# DG5-shield_v1_5.net
KiCad netlist of a schematic drawn in EAGLE
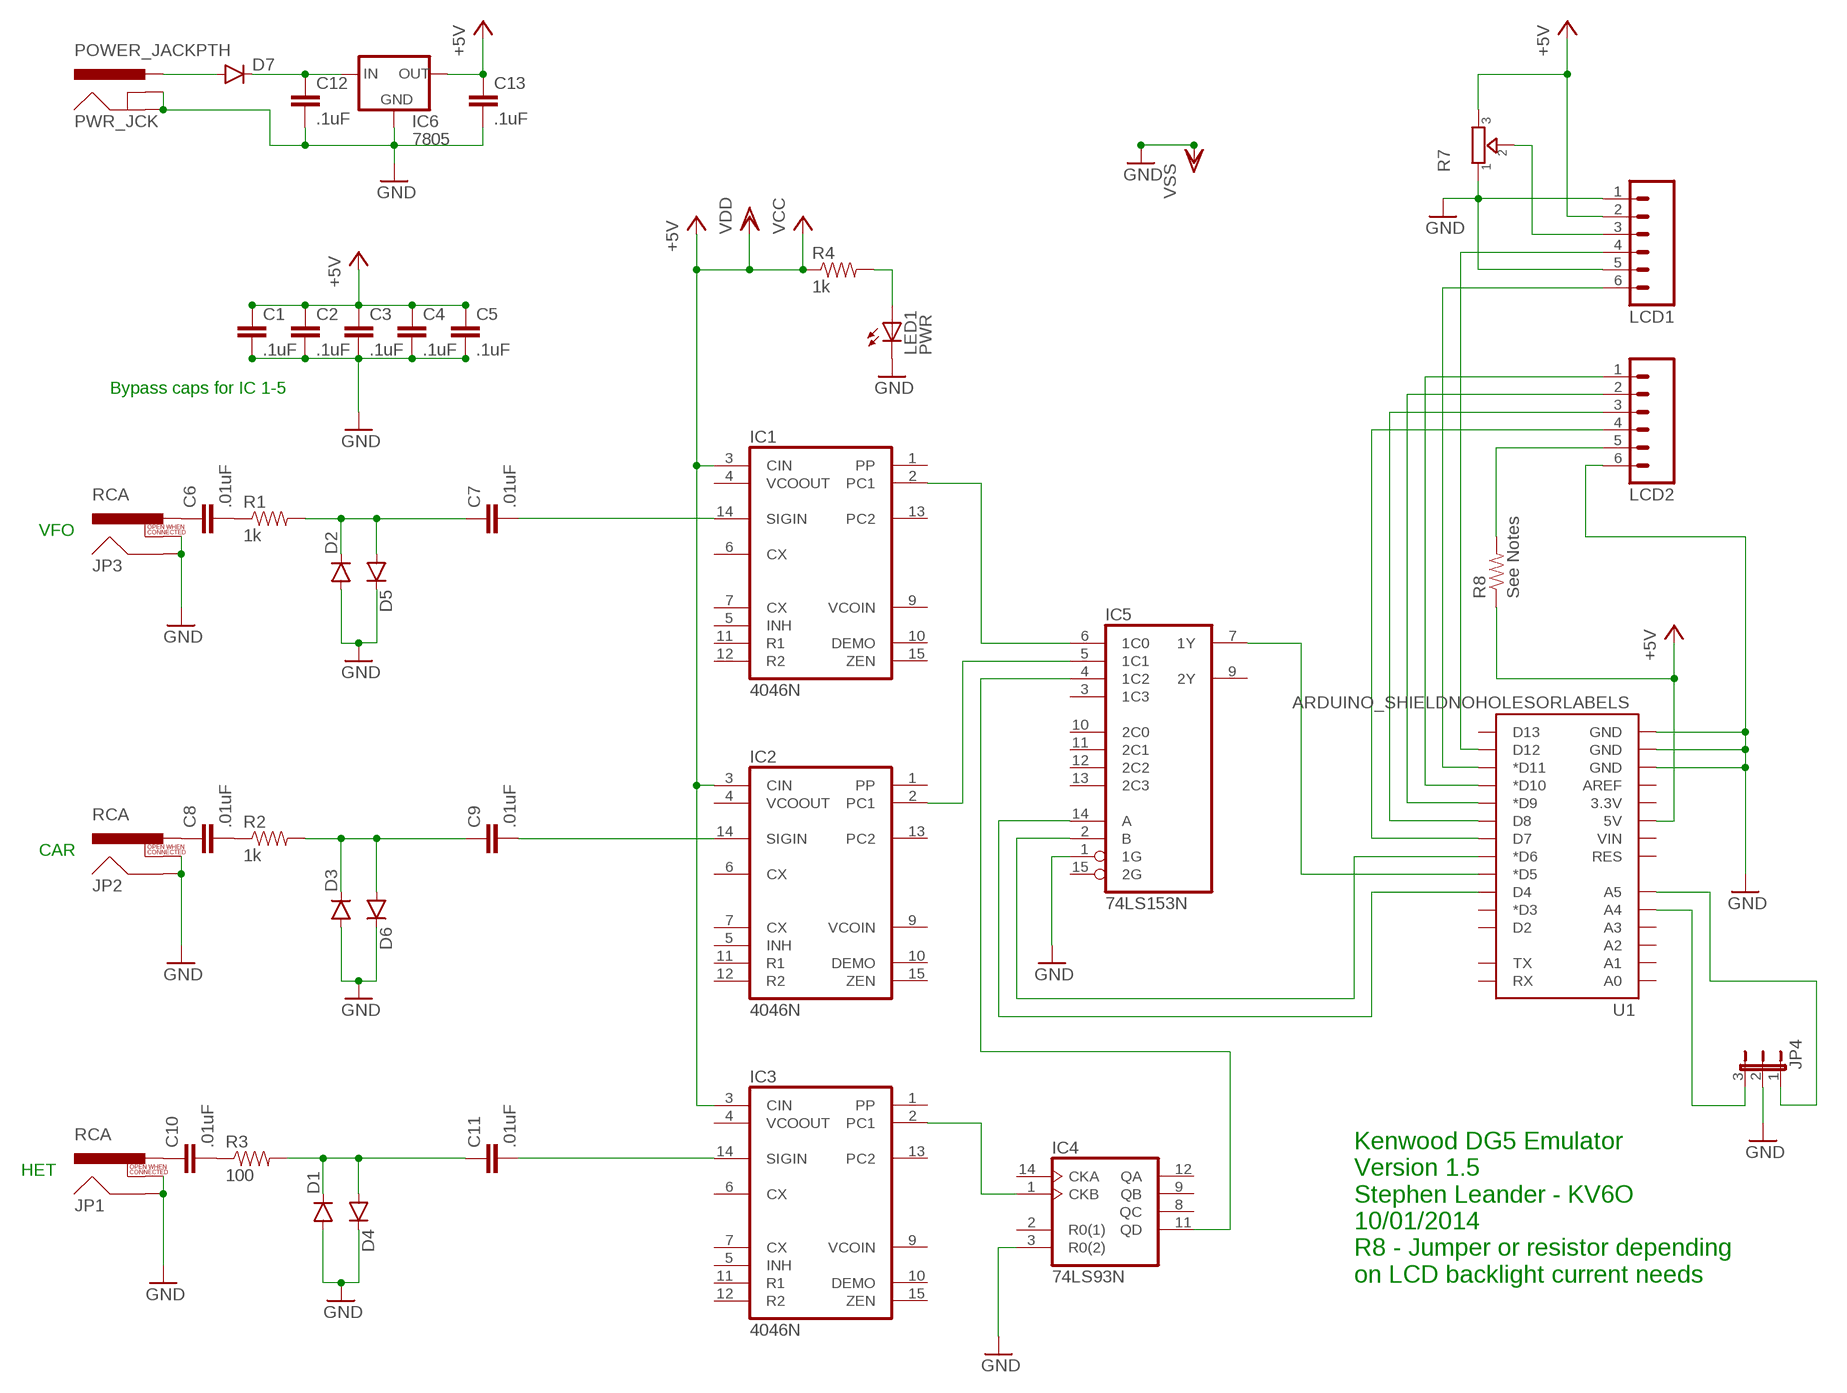
[diagram p0: schematic, sheet 1]

(export (version "E")
  (design (tool "Eeschema 10.0.6"))
  (components
    (comp (ref "C1")
      (value ".1uF")
      (footprint "eagle-import:CAP-PTH-SMALL-KIT")
      (libsource (lib "eagle-import") (part "CAPKIT"))
    )
    (comp (ref "C2")
      (value ".1uF")
      (footprint "eagle-import:CAP-PTH-SMALL-KIT")
      (libsource (lib "eagle-import") (part "CAPKIT"))
    )
    (comp (ref "C3")
      (value ".1uF")
      (footprint "eagle-import:CAP-PTH-SMALL-KIT")
      (libsource (lib "eagle-import") (part "CAPKIT"))
    )
    (comp (ref "C4")
      (value ".1uF")
      (footprint "eagle-import:CAP-PTH-SMALL-KIT")
      (libsource (lib "eagle-import") (part "CAPKIT"))
    )
    (comp (ref "C5")
      (value ".1uF")
      (footprint "eagle-import:CAP-PTH-SMALL-KIT")
      (libsource (lib "eagle-import") (part "CAPKIT"))
    )
    (comp (ref "C6")
      (value ".01uF")
      (footprint "eagle-import:CAP-PTH-SMALL-KIT")
      (libsource (lib "eagle-import") (part "CAPKIT"))
    )
    (comp (ref "C7")
      (value ".01uF")
      (footprint "eagle-import:CAP-PTH-SMALL-KIT")
      (libsource (lib "eagle-import") (part "CAPKIT"))
    )
    (comp (ref "C8")
      (value ".01uF")
      (footprint "eagle-import:CAP-PTH-SMALL-KIT")
      (libsource (lib "eagle-import") (part "CAPKIT"))
    )
    (comp (ref "C9")
      (value ".01uF")
      (footprint "eagle-import:CAP-PTH-SMALL-KIT")
      (libsource (lib "eagle-import") (part "CAPKIT"))
    )
    (comp (ref "C10")
      (value ".01uF")
      (footprint "eagle-import:CAP-PTH-SMALL-KIT")
      (libsource (lib "eagle-import") (part "CAPKIT"))
    )
    (comp (ref "C11")
      (value ".01uF")
      (footprint "eagle-import:CAP-PTH-SMALL-KIT")
      (libsource (lib "eagle-import") (part "CAPKIT"))
    )
    (comp (ref "C12")
      (value ".1uF")
      (footprint "eagle-import:CAP-PTH-SMALL-KIT")
      (libsource (lib "eagle-import") (part "CAPKIT"))
    )
    (comp (ref "C13")
      (value ".1uF")
      (footprint "eagle-import:CAP-PTH-SMALL-KIT")
      (libsource (lib "eagle-import") (part "CAPKIT"))
    )
    (comp (ref "D1")
      (value "DIODE1N4148")
      (footprint "eagle-import:DIODE-1N4148")
      (libsource (lib "eagle-import") (part "DIODE1N4148"))
    )
    (comp (ref "D2")
      (value "DIODE1N4148")
      (footprint "eagle-import:DIODE-1N4148")
      (libsource (lib "eagle-import") (part "DIODE1N4148"))
    )
    (comp (ref "D3")
      (value "DIODE1N4148")
      (footprint "eagle-import:DIODE-1N4148")
      (libsource (lib "eagle-import") (part "DIODE1N4148"))
    )
    (comp (ref "D4")
      (value "DIODE1N4148")
      (footprint "eagle-import:DIODE-1N4148")
      (libsource (lib "eagle-import") (part "DIODE1N4148"))
    )
    (comp (ref "D5")
      (value "DIODE1N4148")
      (footprint "eagle-import:DIODE-1N4148")
      (libsource (lib "eagle-import") (part "DIODE1N4148"))
    )
    (comp (ref "D6")
      (value "DIODE1N4148")
      (footprint "eagle-import:DIODE-1N4148")
      (libsource (lib "eagle-import") (part "DIODE1N4148"))
    )
    (comp (ref "D7")
      (value "DIODE")
      (footprint "eagle-import:DIODE-1N4001-KIT")
      (libsource (lib "eagle-import") (part "DIODE"))
    )
    (comp (ref "IC1")
      (value "4046N")
      (footprint "eagle-import:DIL16")
      (libsource (lib "eagle-import") (part "4046N"))
    )
    (comp (ref "IC2")
      (value "4046N")
      (footprint "eagle-import:DIL16")
      (libsource (lib "eagle-import") (part "4046N"))
    )
    (comp (ref "IC3")
      (value "4046N")
      (footprint "eagle-import:DIL16")
      (libsource (lib "eagle-import") (part "4046N"))
    )
    (comp (ref "IC4")
      (value "74LS93N")
      (footprint "eagle-import:DIL14")
      (libsource (lib "eagle-import") (part "7493NLS"))
    )
    (comp (ref "IC5")
      (value "74LS153N")
      (footprint "eagle-import:DIL16")
      (libsource (lib "eagle-import") (part "74153NLS"))
    )
    (comp (ref "IC6")
      (value "7805")
      (footprint "eagle-import:TO220-IGO")
      (libsource (lib "eagle-import") (part "V_REG_78XXSINK"))
    )
    (comp (ref "JP1")
      (value "RCA")
      (footprint "eagle-import:RCA")
      (libsource (lib "eagle-import") (part "RCA"))
    )
    (comp (ref "JP2")
      (value "RCA")
      (footprint "eagle-import:RCA")
      (libsource (lib "eagle-import") (part "RCA"))
    )
    (comp (ref "JP3")
      (value "RCA")
      (footprint "eagle-import:RCA")
      (libsource (lib "eagle-import") (part "RCA"))
    )
    (comp (ref "JP4")
      (value "JP2E")
      (footprint "eagle-import:JP2")
      (libsource (lib "eagle-import") (part "JP2E"))
    )
    (comp (ref "LCD1")
      (value "M06SIP")
      (footprint "eagle-import:1X06")
      (libsource (lib "eagle-import") (part "M06SIP"))
    )
    (comp (ref "LCD2")
      (value "M06SIP")
      (footprint "eagle-import:1X06")
      (libsource (lib "eagle-import") (part "M06SIP"))
    )
    (comp (ref "LED1")
      (value "PWR")
      (footprint "eagle-import:LED3MM")
      (fields (field (name "MF") "VISHAY SEMICONDUCTOR"))
      (libsource (lib "eagle-import") (part "TLLG4400"))
    )
    (comp (ref "PWR_JCK")
      (value "POWER_JACKPTH")
      (footprint "eagle-import:POWER_JACK_PTH")
      (libsource (lib "eagle-import") (part "POWER_JACKPTH"))
    )
    (comp (ref "R1")
      (value "1k")
      (footprint "eagle-import:1_6W-RES")
      (libsource (lib "eagle-import") (part "RESISTORPTH-1/6W"))
    )
    (comp (ref "R2")
      (value "1k")
      (footprint "eagle-import:1_6W-RES")
      (libsource (lib "eagle-import") (part "RESISTORPTH-1/6W"))
    )
    (comp (ref "R3")
      (value "100")
      (footprint "eagle-import:1_6W-RES")
      (libsource (lib "eagle-import") (part "RESISTORPTH-1/6W"))
    )
    (comp (ref "R4")
      (value "1k")
      (footprint "eagle-import:1_6W-RES")
      (libsource (lib "eagle-import") (part "RESISTORPTH-1/6W"))
    )
    (comp (ref "R7")
      (value "TRIMMER-3306F")
      (footprint "eagle-import:TRIMMER_3306F")
      (libsource (lib "eagle-import") (part "TRIMMER-3306F"))
    )
    (comp (ref "R8")
      (value "See Notes")
      (footprint "eagle-import:1_6W-RES")
      (libsource (lib "eagle-import") (part "RESISTORPTH-1/6W"))
    )
    (comp (ref "U1")
      (value "ARDUINO_SHIELDNOHOLESORLABELS")
      (footprint "eagle-import:DUEMILANOVE_SHIELD_NOHOLES_NOLABELS")
      (libsource (lib "eagle-import") (part "ARDUINO_SHIELDNOHOLESORLABELS"))
    )
  )
  (nets
    (net (code "1") (name "+5V") (class "Default")
      (node (ref "C1") (pin "1") (pinfunction "1_1") (pintype "passive"))
      (node (ref "C13") (pin "1") (pinfunction "1_1") (pintype "passive"))
      (node (ref "C2") (pin "1") (pinfunction "1_1") (pintype "passive"))
      (node (ref "C3") (pin "1") (pinfunction "1_1") (pintype "passive"))
      (node (ref "C4") (pin "1") (pinfunction "1_1") (pintype "passive"))
      (node (ref "C5") (pin "1") (pinfunction "1_1") (pintype "passive"))
      (node (ref "IC1") (pin "3") (pinfunction "CIN_3") (pintype "input"))
      (node (ref "IC2") (pin "3") (pinfunction "CIN_3") (pintype "input"))
      (node (ref "IC3") (pin "3") (pinfunction "CIN_3") (pintype "input"))
      (node (ref "IC6") (pin "OUT") (pinfunction "OUT_OUT") (pintype "output"))
      (node (ref "LCD1") (pin "2") (pinfunction "2_2") (pintype "passive"))
      (node (ref "R4") (pin "1") (pinfunction "1_1") (pintype "passive"))
      (node (ref "R7") (pin "3") (pinfunction "3_3") (pintype "passive"))
      (node (ref "R8") (pin "1") (pinfunction "1_1") (pintype "passive"))
      (node (ref "U1") (pin "5V") (pinfunction "5V_5V") (pintype "bidirectional"))
    )
    (net (code "2") (name "GND") (class "Default")
      (node (ref "C1") (pin "2") (pinfunction "2_2") (pintype "passive"))
      (node (ref "C12") (pin "2") (pinfunction "2_2") (pintype "passive"))
      (node (ref "C13") (pin "2") (pinfunction "2_2") (pintype "passive"))
      (node (ref "C2") (pin "2") (pinfunction "2_2") (pintype "passive"))
      (node (ref "C3") (pin "2") (pinfunction "2_2") (pintype "passive"))
      (node (ref "C4") (pin "2") (pinfunction "2_2") (pintype "passive"))
      (node (ref "C5") (pin "2") (pinfunction "2_2") (pintype "passive"))
      (node (ref "D1") (pin "A") (pinfunction "A_A") (pintype "passive"))
      (node (ref "D2") (pin "A") (pinfunction "A_A") (pintype "passive"))
      (node (ref "D3") (pin "A") (pinfunction "A_A") (pintype "passive"))
      (node (ref "D4") (pin "C") (pinfunction "C_C") (pintype "passive"))
      (node (ref "D5") (pin "C") (pinfunction "C_C") (pintype "passive"))
      (node (ref "D6") (pin "C") (pinfunction "C_C") (pintype "passive"))
      (node (ref "IC4") (pin "3") (pinfunction "R0(2)_3") (pintype "input"))
      (node (ref "IC5") (pin "1") (pinfunction "1G_1") (pintype "input"))
      (node (ref "IC6") (pin "GND") (pinfunction "GND_GND") (pintype "input"))
      (node (ref "JP1") (pin "SHELL") (pinfunction "SHELL_SHELL") (pintype "bidirectional"))
      (node (ref "JP1") (pin "SWITCH") (pinfunction "SWITCH_SWITCH") (pintype "bidirectional"))
      (node (ref "JP2") (pin "SHELL") (pinfunction "SHELL_SHELL") (pintype "bidirectional"))
      (node (ref "JP2") (pin "SWITCH") (pinfunction "SWITCH_SWITCH") (pintype "bidirectional"))
      (node (ref "JP3") (pin "SHELL") (pinfunction "SHELL_SHELL") (pintype "bidirectional"))
      (node (ref "JP3") (pin "SWITCH") (pinfunction "SWITCH_SWITCH") (pintype "bidirectional"))
      (node (ref "JP4") (pin "2") (pinfunction "2_2") (pintype "passive"))
      (node (ref "LCD1") (pin "1") (pinfunction "1_1") (pintype "passive"))
      (node (ref "LCD1") (pin "5") (pinfunction "5_5") (pintype "passive"))
      (node (ref "LCD2") (pin "6") (pinfunction "6_6") (pintype "passive"))
      (node (ref "LED1") (pin "K") (pinfunction "C_K") (pintype "passive"))
      (node (ref "PWR_JCK") (pin "GND") (pinfunction "GND_GND") (pintype "bidirectional"))
      (node (ref "PWR_JCK") (pin "GNDBREAK") (pinfunction "GNDBREAK_GNDBREAK") (pintype "bidirectional"))
      (node (ref "R7") (pin "1") (pinfunction "1_1") (pintype "passive"))
      (node (ref "U1") (pin "GND@0") (pinfunction "GND_GND@0") (pintype "bidirectional"))
      (node (ref "U1") (pin "GND@1") (pinfunction "GND_GND@1") (pintype "bidirectional"))
      (node (ref "U1") (pin "GND@2") (pinfunction "GND_GND@2") (pintype "bidirectional"))
    )
    (net (code "3") (name "Net-(C6-Pad1)") (class "Default")
      (node (ref "C6") (pin "1") (pinfunction "1_1") (pintype "passive"))
      (node (ref "JP3") (pin "PIN") (pinfunction "PIN_PIN") (pintype "bidirectional"))
    )
    (net (code "4") (name "Net-(C6-Pad2)") (class "Default")
      (node (ref "C6") (pin "2") (pinfunction "2_2") (pintype "passive"))
      (node (ref "R1") (pin "1") (pinfunction "1_1") (pintype "passive"))
    )
    (net (code "5") (name "Net-(C7-Pad1)") (class "Default")
      (node (ref "C7") (pin "1") (pinfunction "1_1") (pintype "passive"))
      (node (ref "D2") (pin "C") (pinfunction "C_C") (pintype "passive"))
      (node (ref "D5") (pin "A") (pinfunction "A_A") (pintype "passive"))
      (node (ref "R1") (pin "2") (pinfunction "2_2") (pintype "passive"))
    )
    (net (code "6") (name "Net-(C8-Pad1)") (class "Default")
      (node (ref "C8") (pin "1") (pinfunction "1_1") (pintype "passive"))
      (node (ref "JP2") (pin "PIN") (pinfunction "PIN_PIN") (pintype "bidirectional"))
    )
    (net (code "7") (name "Net-(C8-Pad2)") (class "Default")
      (node (ref "C8") (pin "2") (pinfunction "2_2") (pintype "passive"))
      (node (ref "R2") (pin "1") (pinfunction "1_1") (pintype "passive"))
    )
    (net (code "8") (name "Net-(C9-Pad1)") (class "Default")
      (node (ref "C9") (pin "1") (pinfunction "1_1") (pintype "passive"))
      (node (ref "D3") (pin "C") (pinfunction "C_C") (pintype "passive"))
      (node (ref "D6") (pin "A") (pinfunction "A_A") (pintype "passive"))
      (node (ref "R2") (pin "2") (pinfunction "2_2") (pintype "passive"))
    )
    (net (code "9") (name "Net-(C10-Pad1)") (class "Default")
      (node (ref "C10") (pin "1") (pinfunction "1_1") (pintype "passive"))
      (node (ref "JP1") (pin "PIN") (pinfunction "PIN_PIN") (pintype "bidirectional"))
    )
    (net (code "10") (name "Net-(C10-Pad2)") (class "Default")
      (node (ref "C10") (pin "2") (pinfunction "2_2") (pintype "passive"))
      (node (ref "R3") (pin "1") (pinfunction "1_1") (pintype "passive"))
    )
    (net (code "11") (name "Net-(C11-Pad1)") (class "Default")
      (node (ref "C11") (pin "1") (pinfunction "1_1") (pintype "passive"))
      (node (ref "D1") (pin "C") (pinfunction "C_C") (pintype "passive"))
      (node (ref "D4") (pin "A") (pinfunction "A_A") (pintype "passive"))
      (node (ref "R3") (pin "2") (pinfunction "2_2") (pintype "passive"))
    )
    (net (code "12") (name "Net-(C12-Pad1)") (class "Default")
      (node (ref "C12") (pin "1") (pinfunction "1_1") (pintype "passive"))
      (node (ref "D7") (pin "C") (pinfunction "C_C") (pintype "passive"))
      (node (ref "IC6") (pin "IN") (pinfunction "IN_IN") (pintype "input"))
    )
    (net (code "13") (name "Net-(D7-PadA)") (class "Default")
      (node (ref "D7") (pin "A") (pinfunction "A_A") (pintype "passive"))
      (node (ref "PWR_JCK") (pin "PWR") (pinfunction "PWR_PWR") (pintype "bidirectional"))
    )
    (net (code "14") (name "Net-(IC1A-PC1)") (class "Default")
      (node (ref "IC1") (pin "2") (pinfunction "PC1_2") (pintype "output"))
      (node (ref "IC5") (pin "6") (pinfunction "1C0_6") (pintype "input"))
    )
    (net (code "15") (name "Net-(IC1A-SIGIN)") (class "Default")
      (node (ref "C7") (pin "2") (pinfunction "2_2") (pintype "passive"))
      (node (ref "IC1") (pin "14") (pinfunction "SIGIN_14") (pintype "input"))
    )
    (net (code "16") (name "Net-(IC2A-PC1)") (class "Default")
      (node (ref "IC2") (pin "2") (pinfunction "PC1_2") (pintype "output"))
      (node (ref "IC5") (pin "5") (pinfunction "1C1_5") (pintype "input"))
    )
    (net (code "17") (name "Net-(IC2A-SIGIN)") (class "Default")
      (node (ref "C9") (pin "2") (pinfunction "2_2") (pintype "passive"))
      (node (ref "IC2") (pin "14") (pinfunction "SIGIN_14") (pintype "input"))
    )
    (net (code "18") (name "Net-(IC3A-PC1)") (class "Default")
      (node (ref "IC3") (pin "2") (pinfunction "PC1_2") (pintype "output"))
      (node (ref "IC4") (pin "1") (pinfunction "CKB_1") (pintype "input"))
    )
    (net (code "19") (name "Net-(IC3A-SIGIN)") (class "Default")
      (node (ref "C11") (pin "2") (pinfunction "2_2") (pintype "passive"))
      (node (ref "IC3") (pin "14") (pinfunction "SIGIN_14") (pintype "input"))
    )
    (net (code "20") (name "Net-(IC4A-QD)") (class "Default")
      (node (ref "IC4") (pin "11") (pinfunction "QD_11") (pintype "output"))
      (node (ref "IC5") (pin "4") (pinfunction "1C2_4") (pintype "input"))
    )
    (net (code "21") (name "Net-(IC5A-1Y)") (class "Default")
      (node (ref "IC5") (pin "7") (pinfunction "1Y_7") (pintype "output"))
      (node (ref "U1") (pin "D5") (pinfunction "*D5_D5") (pintype "bidirectional"))
    )
    (net (code "22") (name "Net-(IC5A-A)") (class "Default")
      (node (ref "IC5") (pin "14") (pinfunction "A_14") (pintype "input"))
      (node (ref "U1") (pin "D4") (pinfunction "D4_D4") (pintype "bidirectional"))
    )
    (net (code "23") (name "Net-(IC5A-B)") (class "Default")
      (node (ref "IC5") (pin "2") (pinfunction "B_2") (pintype "input"))
      (node (ref "U1") (pin "D6") (pinfunction "*D6_D6") (pintype "bidirectional"))
    )
    (net (code "24") (name "Net-(JP4-Pad1)") (class "Default")
      (node (ref "JP4") (pin "1") (pinfunction "1_1") (pintype "passive"))
      (node (ref "U1") (pin "A5") (pinfunction "A5_A5") (pintype "bidirectional"))
    )
    (net (code "25") (name "Net-(JP4-Pad3)") (class "Default")
      (node (ref "JP4") (pin "3") (pinfunction "3_3") (pintype "passive"))
      (node (ref "U1") (pin "A4") (pinfunction "A4_A4") (pintype "bidirectional"))
    )
    (net (code "26") (name "Net-(LCD1-Pad3)") (class "Default")
      (node (ref "LCD1") (pin "3") (pinfunction "3_3") (pintype "passive"))
      (node (ref "R7") (pin "2") (pinfunction "2_2") (pintype "passive"))
    )
    (net (code "27") (name "Net-(LCD1-Pad4)") (class "Default")
      (node (ref "LCD1") (pin "4") (pinfunction "4_4") (pintype "passive"))
      (node (ref "U1") (pin "D12") (pinfunction "D12_D12") (pintype "bidirectional"))
    )
    (net (code "28") (name "Net-(LCD2-Pad3)") (class "Default")
      (node (ref "LCD2") (pin "3") (pinfunction "3_3") (pintype "passive"))
      (node (ref "U1") (pin "D8") (pinfunction "D8_D8") (pintype "bidirectional"))
    )
    (net (code "29") (name "Net-(LCD2-Pad4)") (class "Default")
      (node (ref "LCD2") (pin "4") (pinfunction "4_4") (pintype "passive"))
      (node (ref "U1") (pin "D7") (pinfunction "D7_D7") (pintype "bidirectional"))
    )
    (net (code "30") (name "Net-(LCD2-Pad5)") (class "Default")
      (node (ref "LCD2") (pin "5") (pinfunction "5_5") (pintype "passive"))
      (node (ref "R8") (pin "2") (pinfunction "2_2") (pintype "passive"))
    )
    (net (code "31") (name "Net-(LED1-PadA)") (class "Default")
      (node (ref "LED1") (pin "A") (pinfunction "A_A") (pintype "passive"))
      (node (ref "R4") (pin "2") (pinfunction "2_2") (pintype "passive"))
    )
    (net (code "32") (name "Net-(U1-*D9)") (class "Default")
      (node (ref "LCD2") (pin "2") (pinfunction "2_2") (pintype "passive"))
      (node (ref "U1") (pin "D9") (pinfunction "*D9_D9") (pintype "bidirectional"))
    )
    (net (code "33") (name "Net-(U1-*D10)") (class "Default")
      (node (ref "LCD2") (pin "1") (pinfunction "1_1") (pintype "passive"))
      (node (ref "U1") (pin "D10") (pinfunction "*D10_D10") (pintype "bidirectional"))
    )
    (net (code "34") (name "Net-(U1-*D11)") (class "Default")
      (node (ref "LCD1") (pin "6") (pinfunction "6_6") (pintype "passive"))
      (node (ref "U1") (pin "D11") (pinfunction "*D11_D11") (pintype "bidirectional"))
    )
    (net (code "35") (name "unconnected-(IC1A-CX-Pad6)") (class "Default")
      (node (ref "IC1") (pin "6") (pinfunction "CX_6") (pintype "input"))
    )
    (net (code "36") (name "unconnected-(IC1A-CX-Pad7)") (class "Default")
      (node (ref "IC1") (pin "7") (pinfunction "CX_7") (pintype "input"))
    )
    (net (code "37") (name "unconnected-(IC1A-DEMO-Pad10)") (class "Default")
      (node (ref "IC1") (pin "10") (pinfunction "DEMO_10") (pintype "output"))
    )
    (net (code "38") (name "unconnected-(IC1A-INH-Pad5)") (class "Default")
      (node (ref "IC1") (pin "5") (pinfunction "INH_5") (pintype "input"))
    )
    (net (code "39") (name "unconnected-(IC1A-PC2-Pad13)") (class "Default")
      (node (ref "IC1") (pin "13") (pinfunction "PC2_13") (pintype "output"))
    )
    (net (code "40") (name "unconnected-(IC1A-PP-Pad1)") (class "Default")
      (node (ref "IC1") (pin "1") (pinfunction "PP_1") (pintype "output"))
    )
    (net (code "41") (name "unconnected-(IC1A-R1-Pad11)") (class "Default")
      (node (ref "IC1") (pin "11") (pinfunction "R1_11") (pintype "input"))
    )
    (net (code "42") (name "unconnected-(IC1A-R2-Pad12)") (class "Default")
      (node (ref "IC1") (pin "12") (pinfunction "R2_12") (pintype "input"))
    )
    (net (code "43") (name "unconnected-(IC1A-VCOIN-Pad9)") (class "Default")
      (node (ref "IC1") (pin "9") (pinfunction "VCOIN_9") (pintype "input"))
    )
    (net (code "44") (name "unconnected-(IC1A-VCOOUT-Pad4)") (class "Default")
      (node (ref "IC1") (pin "4") (pinfunction "VCOOUT_4") (pintype "output"))
    )
    (net (code "45") (name "unconnected-(IC1A-ZEN-Pad15)") (class "Default")
      (node (ref "IC1") (pin "15") (pinfunction "ZEN_15") (pintype "input"))
    )
    (net (code "46") (name "unconnected-(IC2A-CX-Pad6)") (class "Default")
      (node (ref "IC2") (pin "6") (pinfunction "CX_6") (pintype "input"))
    )
    (net (code "47") (name "unconnected-(IC2A-CX-Pad7)") (class "Default")
      (node (ref "IC2") (pin "7") (pinfunction "CX_7") (pintype "input"))
    )
    (net (code "48") (name "unconnected-(IC2A-DEMO-Pad10)") (class "Default")
      (node (ref "IC2") (pin "10") (pinfunction "DEMO_10") (pintype "output"))
    )
    (net (code "49") (name "unconnected-(IC2A-INH-Pad5)") (class "Default")
      (node (ref "IC2") (pin "5") (pinfunction "INH_5") (pintype "input"))
    )
    (net (code "50") (name "unconnected-(IC2A-PC2-Pad13)") (class "Default")
      (node (ref "IC2") (pin "13") (pinfunction "PC2_13") (pintype "output"))
    )
    (net (code "51") (name "unconnected-(IC2A-PP-Pad1)") (class "Default")
      (node (ref "IC2") (pin "1") (pinfunction "PP_1") (pintype "output"))
    )
    (net (code "52") (name "unconnected-(IC2A-R1-Pad11)") (class "Default")
      (node (ref "IC2") (pin "11") (pinfunction "R1_11") (pintype "input"))
    )
    (net (code "53") (name "unconnected-(IC2A-R2-Pad12)") (class "Default")
      (node (ref "IC2") (pin "12") (pinfunction "R2_12") (pintype "input"))
    )
    (net (code "54") (name "unconnected-(IC2A-VCOIN-Pad9)") (class "Default")
      (node (ref "IC2") (pin "9") (pinfunction "VCOIN_9") (pintype "input"))
    )
    (net (code "55") (name "unconnected-(IC2A-VCOOUT-Pad4)") (class "Default")
      (node (ref "IC2") (pin "4") (pinfunction "VCOOUT_4") (pintype "output"))
    )
    (net (code "56") (name "unconnected-(IC2A-ZEN-Pad15)") (class "Default")
      (node (ref "IC2") (pin "15") (pinfunction "ZEN_15") (pintype "input"))
    )
    (net (code "57") (name "unconnected-(IC3A-CX-Pad6)") (class "Default")
      (node (ref "IC3") (pin "6") (pinfunction "CX_6") (pintype "input"))
    )
    (net (code "58") (name "unconnected-(IC3A-CX-Pad7)") (class "Default")
      (node (ref "IC3") (pin "7") (pinfunction "CX_7") (pintype "input"))
    )
    (net (code "59") (name "unconnected-(IC3A-DEMO-Pad10)") (class "Default")
      (node (ref "IC3") (pin "10") (pinfunction "DEMO_10") (pintype "output"))
    )
    (net (code "60") (name "unconnected-(IC3A-INH-Pad5)") (class "Default")
      (node (ref "IC3") (pin "5") (pinfunction "INH_5") (pintype "input"))
    )
    (net (code "61") (name "unconnected-(IC3A-PC2-Pad13)") (class "Default")
      (node (ref "IC3") (pin "13") (pinfunction "PC2_13") (pintype "output"))
    )
    (net (code "62") (name "unconnected-(IC3A-PP-Pad1)") (class "Default")
      (node (ref "IC3") (pin "1") (pinfunction "PP_1") (pintype "output"))
    )
    (net (code "63") (name "unconnected-(IC3A-R1-Pad11)") (class "Default")
      (node (ref "IC3") (pin "11") (pinfunction "R1_11") (pintype "input"))
    )
    (net (code "64") (name "unconnected-(IC3A-R2-Pad12)") (class "Default")
      (node (ref "IC3") (pin "12") (pinfunction "R2_12") (pintype "input"))
    )
    (net (code "65") (name "unconnected-(IC3A-VCOIN-Pad9)") (class "Default")
      (node (ref "IC3") (pin "9") (pinfunction "VCOIN_9") (pintype "input"))
    )
    (net (code "66") (name "unconnected-(IC3A-VCOOUT-Pad4)") (class "Default")
      (node (ref "IC3") (pin "4") (pinfunction "VCOOUT_4") (pintype "output"))
    )
    (net (code "67") (name "unconnected-(IC3A-ZEN-Pad15)") (class "Default")
      (node (ref "IC3") (pin "15") (pinfunction "ZEN_15") (pintype "input"))
    )
    (net (code "68") (name "unconnected-(IC4A-CKA-Pad14)") (class "Default")
      (node (ref "IC4") (pin "14") (pinfunction "CKA_14") (pintype "input"))
    )
    (net (code "69") (name "unconnected-(IC4A-QA-Pad12)") (class "Default")
      (node (ref "IC4") (pin "12") (pinfunction "QA_12") (pintype "output"))
    )
    (net (code "70") (name "unconnected-(IC4A-QB-Pad9)") (class "Default")
      (node (ref "IC4") (pin "9") (pinfunction "QB_9") (pintype "output"))
    )
    (net (code "71") (name "unconnected-(IC4A-QC-Pad8)") (class "Default")
      (node (ref "IC4") (pin "8") (pinfunction "QC_8") (pintype "output"))
    )
    (net (code "72") (name "unconnected-(IC4A-R0(1)-Pad2)") (class "Default")
      (node (ref "IC4") (pin "2") (pinfunction "R0(1)_2") (pintype "input"))
    )
    (net (code "73") (name "unconnected-(IC5A-1C3-Pad3)") (class "Default")
      (node (ref "IC5") (pin "3") (pinfunction "1C3_3") (pintype "input"))
    )
    (net (code "74") (name "unconnected-(IC5A-2C0-Pad10)") (class "Default")
      (node (ref "IC5") (pin "10") (pinfunction "2C0_10") (pintype "input"))
    )
    (net (code "75") (name "unconnected-(IC5A-2C1-Pad11)") (class "Default")
      (node (ref "IC5") (pin "11") (pinfunction "2C1_11") (pintype "input"))
    )
    (net (code "76") (name "unconnected-(IC5A-2C2-Pad12)") (class "Default")
      (node (ref "IC5") (pin "12") (pinfunction "2C2_12") (pintype "input"))
    )
    (net (code "77") (name "unconnected-(IC5A-2C3-Pad13)") (class "Default")
      (node (ref "IC5") (pin "13") (pinfunction "2C3_13") (pintype "input"))
    )
    (net (code "78") (name "unconnected-(IC5A-2G-Pad15)") (class "Default")
      (node (ref "IC5") (pin "15") (pinfunction "2G_15") (pintype "input"))
    )
    (net (code "79") (name "unconnected-(IC5A-2Y-Pad9)") (class "Default")
      (node (ref "IC5") (pin "9") (pinfunction "2Y_9") (pintype "output"))
    )
    (net (code "80") (name "unconnected-(U1-*D3-PadD3)") (class "Default")
      (node (ref "U1") (pin "D3") (pinfunction "*D3_D3") (pintype "bidirectional"))
    )
    (net (code "81") (name "unconnected-(U1-Pad3.3V)") (class "Default")
      (node (ref "U1") (pin "3.3V") (pinfunction "3.3V_3.3V") (pintype "bidirectional"))
    )
    (net (code "82") (name "unconnected-(U1-PadA0)") (class "Default")
      (node (ref "U1") (pin "A0") (pinfunction "A0_A0") (pintype "bidirectional"))
    )
    (net (code "83") (name "unconnected-(U1-PadA1)") (class "Default")
      (node (ref "U1") (pin "A1") (pinfunction "A1_A1") (pintype "bidirectional"))
    )
    (net (code "84") (name "unconnected-(U1-PadA2)") (class "Default")
      (node (ref "U1") (pin "A2") (pinfunction "A2_A2") (pintype "bidirectional"))
    )
    (net (code "85") (name "unconnected-(U1-PadA3)") (class "Default")
      (node (ref "U1") (pin "A3") (pinfunction "A3_A3") (pintype "bidirectional"))
    )
    (net (code "86") (name "unconnected-(U1-PadAREF)") (class "Default")
      (node (ref "U1") (pin "AREF") (pinfunction "AREF_AREF") (pintype "bidirectional"))
    )
    (net (code "87") (name "unconnected-(U1-PadD2)") (class "Default")
      (node (ref "U1") (pin "D2") (pinfunction "D2_D2") (pintype "bidirectional"))
    )
    (net (code "88") (name "unconnected-(U1-PadD13)") (class "Default")
      (node (ref "U1") (pin "D13") (pinfunction "D13_D13") (pintype "bidirectional"))
    )
    (net (code "89") (name "unconnected-(U1-PadRES)") (class "Default")
      (node (ref "U1") (pin "RES") (pinfunction "RES_RES") (pintype "bidirectional"))
    )
    (net (code "90") (name "unconnected-(U1-PadRX)") (class "Default")
      (node (ref "U1") (pin "RX") (pinfunction "RX_RX") (pintype "bidirectional"))
    )
    (net (code "91") (name "unconnected-(U1-PadTX)") (class "Default")
      (node (ref "U1") (pin "TX") (pinfunction "TX_TX") (pintype "bidirectional"))
    )
    (net (code "92") (name "unconnected-(U1-PadVIN)") (class "Default")
      (node (ref "U1") (pin "VIN") (pinfunction "VIN_VIN") (pintype "bidirectional"))
    )
  )
)
